# Servo-Power.net
KiCad netlist of a schematic drawn in Altium Designer
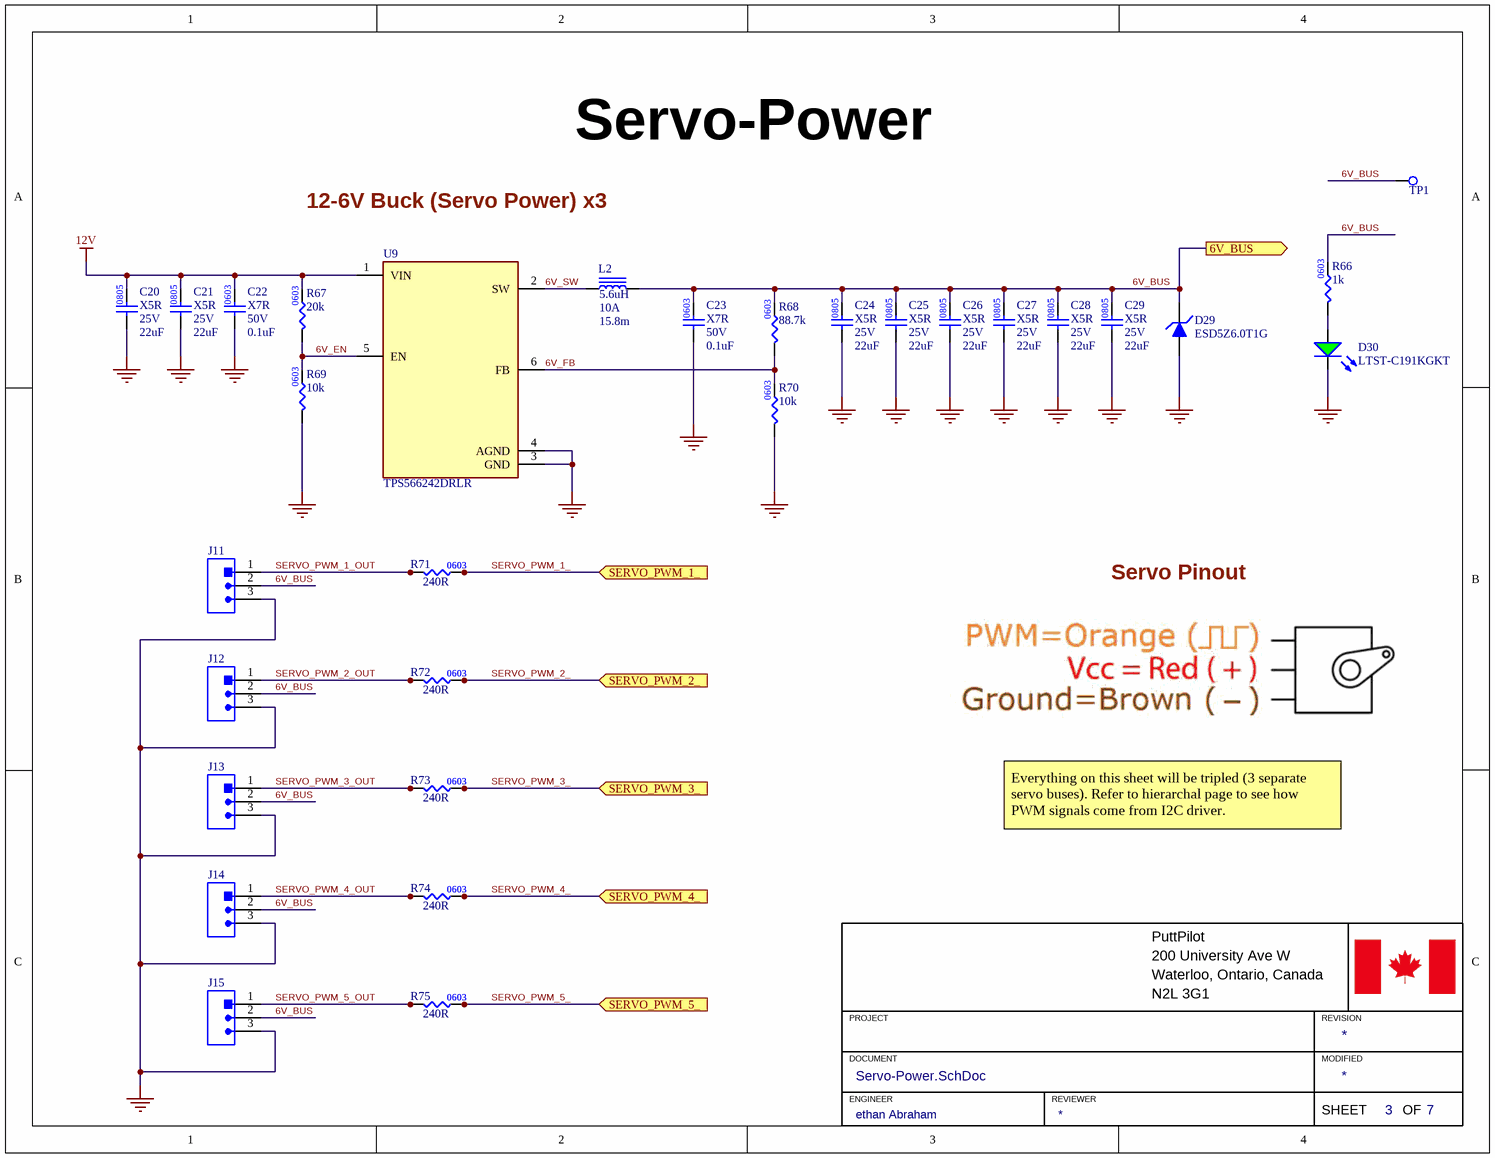
[diagram p0: Servo-Power.SchDoc]

(export (version "E")
  (design (tool "Eeschema 10.0.6"))
  (components
    (comp (ref "C20")
      (value "GRM21BR61E226ME44K")
      (footprint ".CAP_0805")
      (description "CAP CER 22uF 25V X5R 0805")
      (fields
        (field (name "MANUFACTURER") "Murata")
        (field (name "TEMPERATURE CHARACTERISTICS CODE") "X5R")
        (field (name "RATED DC VOLTAGE (URDC)") "25V")
        (field (name "CAPACITANCE") "22uF")
      )
      (libsource (lib "PuttPilot") (part "GRM21BR61E226ME44K"))
    )
    (comp (ref "C21")
      (value "GRM21BR61E226ME44K")
      (footprint ".CAP_0805")
      (description "CAP CER 22uF 25V X5R 0805")
      (fields
        (field (name "MANUFACTURER") "Murata")
        (field (name "TEMPERATURE CHARACTERISTICS CODE") "X5R")
        (field (name "RATED DC VOLTAGE (URDC)") "25V")
        (field (name "CAPACITANCE") "22uF")
      )
      (libsource (lib "PuttPilot") (part "GRM21BR61E226ME44K"))
    )
    (comp (ref "C22")
      (value "GCJ188R71H104KA12D")
      (footprint ".CAP_0603")
      (description "CAP CER 0.1uF 50V X7R 0603")
      (fields
        (field (name "MANUFACTURER") "Murata")
        (field (name "TEMPERATURE CHARACTERISTICS CODE") "X7R")
        (field (name "RATED DC VOLTAGE (URDC)") "50V")
        (field (name "CAPACITANCE") "0.1uF")
      )
      (libsource (lib "PuttPilot") (part "GCJ188R71H104KA12D"))
    )
    (comp (ref "C23")
      (value "GCJ188R71H104KA12D")
      (footprint ".CAP_0603")
      (description "CAP CER 0.1uF 50V X7R 0603")
      (fields
        (field (name "MANUFACTURER") "Murata")
        (field (name "TEMPERATURE CHARACTERISTICS CODE") "X7R")
        (field (name "RATED DC VOLTAGE (URDC)") "50V")
        (field (name "CAPACITANCE") "0.1uF")
      )
      (libsource (lib "PuttPilot") (part "GCJ188R71H104KA12D"))
    )
    (comp (ref "C24")
      (value "GRM21BR61E226ME44K")
      (footprint ".CAP_0805")
      (description "CAP CER 22uF 25V X5R 0805")
      (fields
        (field (name "MANUFACTURER") "Murata")
        (field (name "TEMPERATURE CHARACTERISTICS CODE") "X5R")
        (field (name "RATED DC VOLTAGE (URDC)") "25V")
        (field (name "CAPACITANCE") "22uF")
      )
      (libsource (lib "PuttPilot") (part "GRM21BR61E226ME44K"))
    )
    (comp (ref "C25")
      (value "GRM21BR61E226ME44K")
      (footprint ".CAP_0805")
      (description "CAP CER 22uF 25V X5R 0805")
      (fields
        (field (name "MANUFACTURER") "Murata")
        (field (name "TEMPERATURE CHARACTERISTICS CODE") "X5R")
        (field (name "RATED DC VOLTAGE (URDC)") "25V")
        (field (name "CAPACITANCE") "22uF")
      )
      (libsource (lib "PuttPilot") (part "GRM21BR61E226ME44K"))
    )
    (comp (ref "C26")
      (value "GRM21BR61E226ME44K")
      (footprint ".CAP_0805")
      (description "CAP CER 22uF 25V X5R 0805")
      (fields
        (field (name "MANUFACTURER") "Murata")
        (field (name "TEMPERATURE CHARACTERISTICS CODE") "X5R")
        (field (name "RATED DC VOLTAGE (URDC)") "25V")
        (field (name "CAPACITANCE") "22uF")
      )
      (libsource (lib "PuttPilot") (part "GRM21BR61E226ME44K"))
    )
    (comp (ref "C27")
      (value "GRM21BR61E226ME44K")
      (footprint ".CAP_0805")
      (description "CAP CER 22uF 25V X5R 0805")
      (fields
        (field (name "MANUFACTURER") "Murata")
        (field (name "TEMPERATURE CHARACTERISTICS CODE") "X5R")
        (field (name "RATED DC VOLTAGE (URDC)") "25V")
        (field (name "CAPACITANCE") "22uF")
      )
      (libsource (lib "PuttPilot") (part "GRM21BR61E226ME44K"))
    )
    (comp (ref "C28")
      (value "GRM21BR61E226ME44K")
      (footprint ".CAP_0805")
      (description "CAP CER 22uF 25V X5R 0805")
      (fields
        (field (name "MANUFACTURER") "Murata")
        (field (name "TEMPERATURE CHARACTERISTICS CODE") "X5R")
        (field (name "RATED DC VOLTAGE (URDC)") "25V")
        (field (name "CAPACITANCE") "22uF")
      )
      (libsource (lib "PuttPilot") (part "GRM21BR61E226ME44K"))
    )
    (comp (ref "C29")
      (value "GRM21BR61E226ME44K")
      (footprint ".CAP_0805")
      (description "CAP CER 22uF 25V X5R 0805")
      (fields
        (field (name "MANUFACTURER") "Murata")
        (field (name "TEMPERATURE CHARACTERISTICS CODE") "X5R")
        (field (name "RATED DC VOLTAGE (URDC)") "25V")
        (field (name "CAPACITANCE") "22uF")
      )
      (libsource (lib "PuttPilot") (part "GRM21BR61E226ME44K"))
    )
    (comp (ref "D29")
      (value "ESD5Z6.0T1G")
      (footprint "ESD5Z6.0T1G")
      (description "DIODE TVS 6VWM")
      (fields (field (name "MANUFACTURER") "ON Semiconductor"))
      (libsource (lib "PuttPilot") (part "ESD5Z6.0T1G"))
    )
    (comp (ref "D30")
      (value "LTST-C191KGKT")
      (footprint ".LED_0603")
      (description "LED GREEN 2V 0603")
      (fields (field (name "MANUFACTURER") "Vishay Lite-On"))
      (libsource (lib "PuttPilot") (part "LTST-C191KGKT"))
    )
    (comp (ref "J11")
      (value "TSW-101-08-G-T-RA")
      (footprint "HEADER_3POS_R/A_2.54MM")
      (description "CONN HEADER R/A 3POS 2.54MM")
      (libsource (lib "PuttPilot") (part "TSW-101-08-G-T-RA"))
    )
    (comp (ref "J12")
      (value "TSW-101-08-G-T-RA")
      (footprint "HEADER_3POS_R/A_2.54MM")
      (description "CONN HEADER R/A 3POS 2.54MM")
      (libsource (lib "PuttPilot") (part "TSW-101-08-G-T-RA"))
    )
    (comp (ref "J13")
      (value "TSW-101-08-G-T-RA")
      (footprint "HEADER_3POS_R/A_2.54MM")
      (description "CONN HEADER R/A 3POS 2.54MM")
      (libsource (lib "PuttPilot") (part "TSW-101-08-G-T-RA"))
    )
    (comp (ref "J14")
      (value "TSW-101-08-G-T-RA")
      (footprint "HEADER_3POS_R/A_2.54MM")
      (description "CONN HEADER R/A 3POS 2.54MM")
      (libsource (lib "PuttPilot") (part "TSW-101-08-G-T-RA"))
    )
    (comp (ref "J15")
      (value "TSW-101-08-G-T-RA")
      (footprint "HEADER_3POS_R/A_2.54MM")
      (description "CONN HEADER R/A 3POS 2.54MM")
      (libsource (lib "PuttPilot") (part "TSW-101-08-G-T-RA"))
    )
    (comp (ref "L2")
      (value "SRP6060FA-5R6M")
      (footprint "SRP6060FA-5R6M")
      (description "FIXED IND 5.6uH 10A 15.8mOhm")
      (fields
        (field (name "MANUFACTURER") "Bourns")
        (field (name "INDUCTANCE") "5.6uH")
        (field (name "CURRENT RATING") "10A")
        (field (name "DC RESISTANCE") "15.8m")
      )
      (libsource (lib "PuttPilot") (part "SRP6060FA-5R6M"))
    )
    (comp (ref "R66")
      (value "RC0603FR-071KL")
      (footprint ".RES_0603")
      (description "RES 1K OHM 0603")
      (fields
        (field (name "MANUFACTURER") "Yageo")
        (field (name "TOLERANCE") "1%")
        (field (name "RESISTANCE") "1k")
      )
      (libsource (lib "PuttPilot") (part "RC0603FR-071KL"))
    )
    (comp (ref "R67")
      (value "ERJ-3EKF2002V")
      (footprint ".RES_0603")
      (description "RES 20K OHM 0603")
      (fields
        (field (name "MANUFACTURER") "Panasonic")
        (field (name "TOLERANCE") "1%")
        (field (name "RESISTANCE") "20k")
      )
      (libsource (lib "PuttPilot") (part "ERJ-3EKF2002V"))
    )
    (comp (ref "R68")
      (value "RC0603FR-0788K7L")
      (footprint ".RES_0603")
      (description "RES 88.7K OHM 0603")
      (fields
        (field (name "MANUFACTURER") "Yageo")
        (field (name "TOLERANCE") "1%")
        (field (name "RESISTANCE") "88.7k")
      )
      (libsource (lib "PuttPilot") (part "RC0603FR-0788K7L"))
    )
    (comp (ref "R69")
      (value "RC0603FR-0710KL")
      (footprint ".RES_0603")
      (description "RES 10K OHM 0603")
      (fields
        (field (name "MANUFACTURER") "Yageo")
        (field (name "TOLERANCE") "1%")
        (field (name "RESISTANCE") "10k")
      )
      (libsource (lib "PuttPilot") (part "RC0603FR-0710KL"))
    )
    (comp (ref "R70")
      (value "RC0603FR-0710KL")
      (footprint ".RES_0603")
      (description "RES 10K OHM 0603")
      (fields
        (field (name "MANUFACTURER") "Yageo")
        (field (name "TOLERANCE") "1%")
        (field (name "RESISTANCE") "10k")
      )
      (libsource (lib "PuttPilot") (part "RC0603FR-0710KL"))
    )
    (comp (ref "R71")
      (value "RC0603FR-07240RL")
      (footprint ".RES_0603")
      (description "RES 240 OHM 0603")
      (fields
        (field (name "MANUFACTURER") "Yageo")
        (field (name "TOLERANCE") "1%")
        (field (name "RESISTANCE") "240R")
      )
      (libsource (lib "PuttPilot") (part "RC0603FR-07240RL"))
    )
    (comp (ref "R72")
      (value "RC0603FR-07240RL")
      (footprint ".RES_0603")
      (description "RES 240 OHM 0603")
      (fields
        (field (name "MANUFACTURER") "Yageo")
        (field (name "TOLERANCE") "1%")
        (field (name "RESISTANCE") "240R")
      )
      (libsource (lib "PuttPilot") (part "RC0603FR-07240RL"))
    )
    (comp (ref "R73")
      (value "RC0603FR-07240RL")
      (footprint ".RES_0603")
      (description "RES 240 OHM 0603")
      (fields
        (field (name "MANUFACTURER") "Yageo")
        (field (name "TOLERANCE") "1%")
        (field (name "RESISTANCE") "240R")
      )
      (libsource (lib "PuttPilot") (part "RC0603FR-07240RL"))
    )
    (comp (ref "R74")
      (value "RC0603FR-07240RL")
      (footprint ".RES_0603")
      (description "RES 240 OHM 0603")
      (fields
        (field (name "MANUFACTURER") "Yageo")
        (field (name "TOLERANCE") "1%")
        (field (name "RESISTANCE") "240R")
      )
      (libsource (lib "PuttPilot") (part "RC0603FR-07240RL"))
    )
    (comp (ref "R75")
      (value "RC0603FR-07240RL")
      (footprint ".RES_0603")
      (description "RES 240 OHM 0603")
      (fields
        (field (name "MANUFACTURER") "Yageo")
        (field (name "TOLERANCE") "1%")
        (field (name "RESISTANCE") "240R")
      )
      (libsource (lib "PuttPilot") (part "RC0603FR-07240RL"))
    )
    (comp (ref "TP1")
      (value "RCWCTE")
      (footprint "RCWCTE")
      (description "SMT Test Point")
      (fields (field (name "MANUFACTURER") "KOA Speer"))
      (libsource (lib "PuttPilot") (part "RCWCTE"))
    )
    (comp (ref "U9")
      (value "TPS566242DRLR")
      (footprint "TPS566242DRLR")
      (description "BUCK 3V-16V 6A SOT-563")
      (fields (field (name "MANUFACTURER") "Texas Instruments"))
      (libsource (lib "PuttPilot") (part "TPS566242DRLR"))
    )
  )
  (nets
    (net (code "1") (name "/6V_BUS") (class "Default")
      (node (ref "C23") (pin "2") (pinfunction "2_2") (pintype "passive"))
      (node (ref "C24") (pin "2") (pinfunction "2_2") (pintype "passive"))
      (node (ref "C25") (pin "2") (pinfunction "2_2") (pintype "passive"))
      (node (ref "C26") (pin "2") (pinfunction "2_2") (pintype "passive"))
      (node (ref "C27") (pin "2") (pinfunction "2_2") (pintype "passive"))
      (node (ref "C28") (pin "2") (pinfunction "2_2") (pintype "passive"))
      (node (ref "C29") (pin "2") (pinfunction "2_2") (pintype "passive"))
      (node (ref "D29") (pin "1") (pinfunction "Cathode_1") (pintype "passive"))
      (node (ref "J11") (pin "2") (pinfunction "2_2") (pintype "passive"))
      (node (ref "J12") (pin "2") (pinfunction "2_2") (pintype "passive"))
      (node (ref "J13") (pin "2") (pinfunction "2_2") (pintype "passive"))
      (node (ref "J14") (pin "2") (pinfunction "2_2") (pintype "passive"))
      (node (ref "J15") (pin "2") (pinfunction "2_2") (pintype "passive"))
      (node (ref "L2") (pin "2") (pinfunction "2_2") (pintype "passive"))
      (node (ref "R66") (pin "2") (pinfunction "2_2") (pintype "passive"))
      (node (ref "R68") (pin "2") (pinfunction "2_2") (pintype "passive"))
      (node (ref "TP1") (pin "1") (pinfunction "1_1") (pintype "passive"))
    )
    (net (code "2") (name "/6V_EN") (class "Default")
      (node (ref "R67") (pin "1") (pinfunction "1_1") (pintype "passive"))
      (node (ref "R69") (pin "2") (pinfunction "2_2") (pintype "passive"))
      (node (ref "U9") (pin "5") (pinfunction "EN_5") (pintype "passive"))
    )
    (net (code "3") (name "/6V_FB") (class "Default")
      (node (ref "R68") (pin "1") (pinfunction "1_1") (pintype "passive"))
      (node (ref "R70") (pin "2") (pinfunction "2_2") (pintype "passive"))
      (node (ref "U9") (pin "6") (pinfunction "FB_6") (pintype "passive"))
    )
    (net (code "4") (name "/6V_SW") (class "Default")
      (node (ref "L2") (pin "1") (pinfunction "1_1") (pintype "passive"))
      (node (ref "U9") (pin "2") (pinfunction "SW_2") (pintype "passive"))
    )
    (net (code "5") (name "/SERVO_PWM_1_") (class "Default")
      (node (ref "R71") (pin "2") (pinfunction "2_2") (pintype "passive"))
    )
    (net (code "6") (name "/SERVO_PWM_1_OUT") (class "Default")
      (node (ref "J11") (pin "1") (pinfunction "1_1") (pintype "passive"))
      (node (ref "R71") (pin "1") (pinfunction "1_1") (pintype "passive"))
    )
    (net (code "7") (name "/SERVO_PWM_2_") (class "Default")
      (node (ref "R72") (pin "2") (pinfunction "2_2") (pintype "passive"))
    )
    (net (code "8") (name "/SERVO_PWM_2_OUT") (class "Default")
      (node (ref "J12") (pin "1") (pinfunction "1_1") (pintype "passive"))
      (node (ref "R72") (pin "1") (pinfunction "1_1") (pintype "passive"))
    )
    (net (code "9") (name "/SERVO_PWM_3_") (class "Default")
      (node (ref "R73") (pin "2") (pinfunction "2_2") (pintype "passive"))
    )
    (net (code "10") (name "/SERVO_PWM_3_OUT") (class "Default")
      (node (ref "J13") (pin "1") (pinfunction "1_1") (pintype "passive"))
      (node (ref "R73") (pin "1") (pinfunction "1_1") (pintype "passive"))
    )
    (net (code "11") (name "/SERVO_PWM_4_") (class "Default")
      (node (ref "R74") (pin "2") (pinfunction "2_2") (pintype "passive"))
    )
    (net (code "12") (name "/SERVO_PWM_4_OUT") (class "Default")
      (node (ref "J14") (pin "1") (pinfunction "1_1") (pintype "passive"))
      (node (ref "R74") (pin "1") (pinfunction "1_1") (pintype "passive"))
    )
    (net (code "13") (name "/SERVO_PWM_5_") (class "Default")
      (node (ref "R75") (pin "2") (pinfunction "2_2") (pintype "passive"))
    )
    (net (code "14") (name "/SERVO_PWM_5_OUT") (class "Default")
      (node (ref "J15") (pin "1") (pinfunction "1_1") (pintype "passive"))
      (node (ref "R75") (pin "1") (pinfunction "1_1") (pintype "passive"))
    )
    (net (code "15") (name "12V") (class "Default")
      (node (ref "C20") (pin "2") (pinfunction "2_2") (pintype "passive"))
      (node (ref "C21") (pin "2") (pinfunction "2_2") (pintype "passive"))
      (node (ref "C22") (pin "2") (pinfunction "2_2") (pintype "passive"))
      (node (ref "R67") (pin "2") (pinfunction "2_2") (pintype "passive"))
      (node (ref "U9") (pin "1") (pinfunction "VIN_1") (pintype "passive"))
    )
    (net (code "16") (name "GND") (class "Default")
      (node (ref "C20") (pin "1") (pinfunction "1_1") (pintype "passive"))
      (node (ref "C21") (pin "1") (pinfunction "1_1") (pintype "passive"))
      (node (ref "C22") (pin "1") (pinfunction "1_1") (pintype "passive"))
      (node (ref "C23") (pin "1") (pinfunction "1_1") (pintype "passive"))
      (node (ref "C24") (pin "1") (pinfunction "1_1") (pintype "passive"))
      (node (ref "C25") (pin "1") (pinfunction "1_1") (pintype "passive"))
      (node (ref "C26") (pin "1") (pinfunction "1_1") (pintype "passive"))
      (node (ref "C27") (pin "1") (pinfunction "1_1") (pintype "passive"))
      (node (ref "C28") (pin "1") (pinfunction "1_1") (pintype "passive"))
      (node (ref "C29") (pin "1") (pinfunction "1_1") (pintype "passive"))
      (node (ref "D29") (pin "2") (pinfunction "Anode_2") (pintype "passive"))
      (node (ref "D30") (pin "2") (pinfunction "K_2") (pintype "passive"))
      (node (ref "J11") (pin "3") (pinfunction "3_3") (pintype "passive"))
      (node (ref "J12") (pin "3") (pinfunction "3_3") (pintype "passive"))
      (node (ref "J13") (pin "3") (pinfunction "3_3") (pintype "passive"))
      (node (ref "J14") (pin "3") (pinfunction "3_3") (pintype "passive"))
      (node (ref "J15") (pin "3") (pinfunction "3_3") (pintype "passive"))
      (node (ref "R69") (pin "1") (pinfunction "1_1") (pintype "passive"))
      (node (ref "R70") (pin "1") (pinfunction "1_1") (pintype "passive"))
      (node (ref "U9") (pin "3") (pinfunction "GND_3") (pintype "passive"))
      (node (ref "U9") (pin "4") (pinfunction "AGND_4") (pintype "passive"))
    )
    (net (code "17") (name "Net-(D30-A)") (class "Default")
      (node (ref "D30") (pin "1") (pinfunction "A_1") (pintype "passive"))
      (node (ref "R66") (pin "1") (pinfunction "1_1") (pintype "passive"))
    )
  )
)
